# robomow_city120_terminal.net
KiCad netlist of a schematic drawn in EAGLE
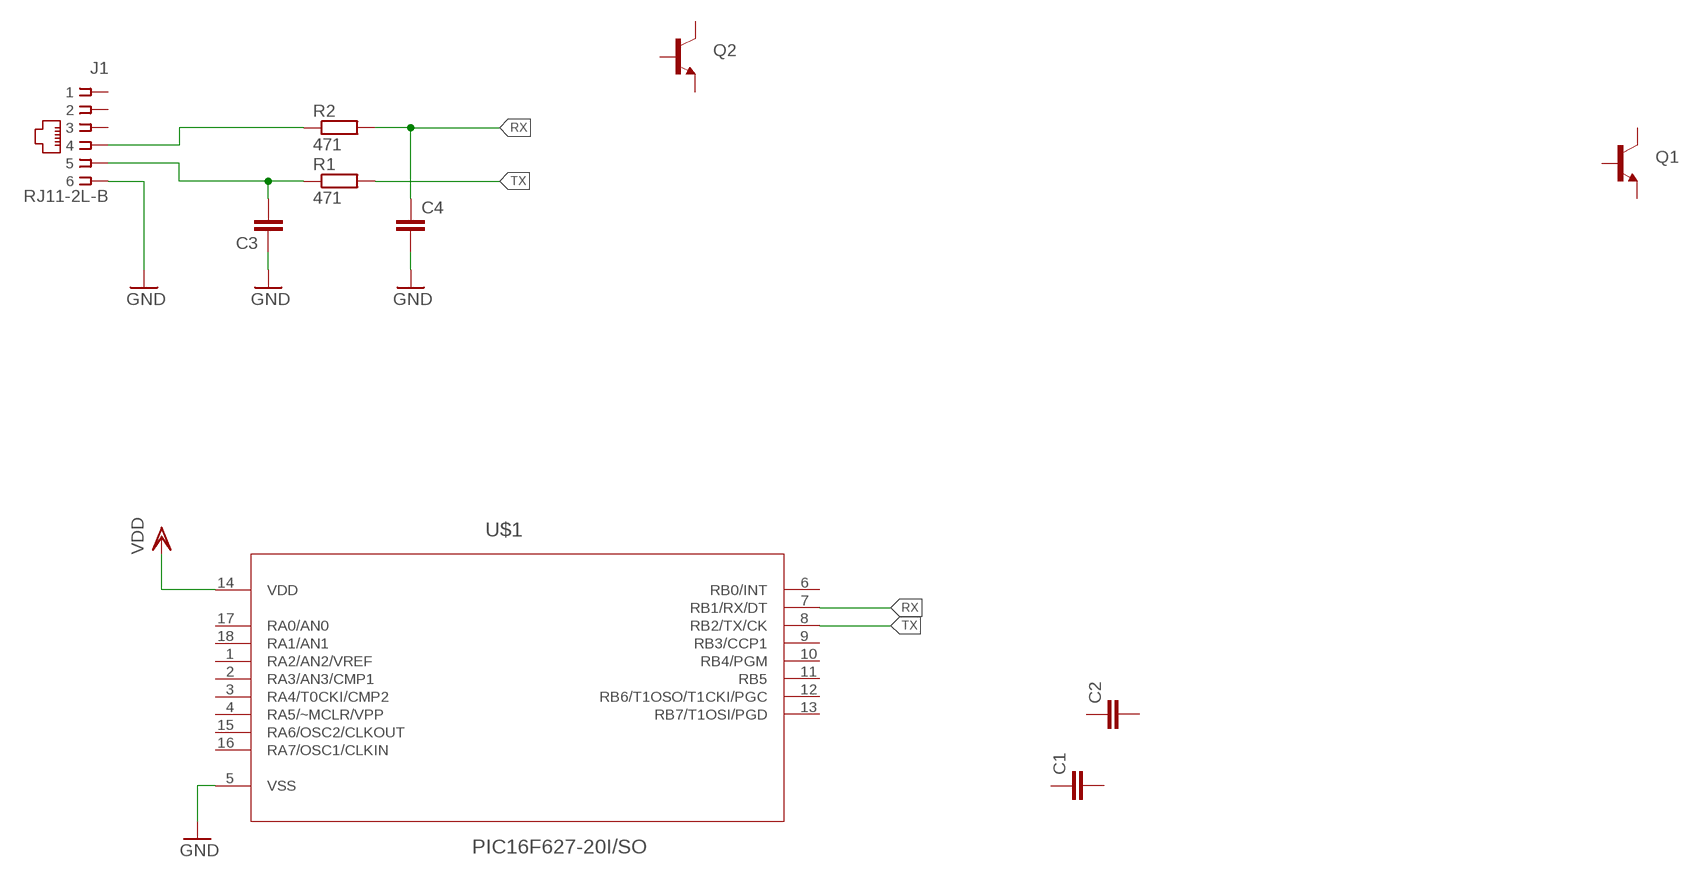
[diagram p0: schematic, sheet 1]

(export (version "E")
  (design (tool "Eeschema 10.0.6"))
  (components
    (comp (ref "C1")
      (value "C-EUC0805")
      (footprint "eagle-import:C0805")
      (libsource (lib "eagle-import") (part "C-EUC0805"))
    )
    (comp (ref "C2")
      (value "C-EUC0805")
      (footprint "eagle-import:C0805")
      (libsource (lib "eagle-import") (part "C-EUC0805"))
    )
    (comp (ref "C3")
      (value "C-EUC0805")
      (footprint "eagle-import:C0805")
      (libsource (lib "eagle-import") (part "C-EUC0805"))
    )
    (comp (ref "C4")
      (value "C-EUC0805")
      (footprint "eagle-import:C0805")
      (libsource (lib "eagle-import") (part "C-EUC0805"))
    )
    (comp (ref "J1")
      (value "RJ11-2L-B")
      (footprint "eagle-import:RJ11-NO_SHIELD")
      (fields (field (name "MF") "TYCO ELECTRONICS"))
      (libsource (lib "eagle-import") (part "RJ11-2L-B"))
    )
    (comp (ref "Q1")
      (value "TRANSISTOR_NPNSOT89")
      (footprint "eagle-import:SOT89")
      (libsource (lib "eagle-import") (part "TRANSISTOR_NPNSOT89"))
    )
    (comp (ref "Q2")
      (value "TRANSISTOR_NPNSOT89")
      (footprint "eagle-import:SOT89")
      (libsource (lib "eagle-import") (part "TRANSISTOR_NPNSOT89"))
    )
    (comp (ref "R1")
      (value "471")
      (footprint "eagle-import:R0805")
      (libsource (lib "eagle-import") (part "R-EU_R0805"))
    )
    (comp (ref "R2")
      (value "471")
      (footprint "eagle-import:R0805")
      (libsource (lib "eagle-import") (part "R-EU_R0805"))
    )
    (comp (ref "U$1")
      (value "PIC16F627-20I/SO")
      (footprint "eagle-import:SOIC127P1030X265-18N")
      (libsource (lib "eagle-import") (part "PIC16F627-20I/SO"))
    )
  )
  (nets
    (net (code "1") (name "GND") (class "Default")
      (node (ref "C3") (pin "1") (pinfunction "1_1") (pintype "passive"))
      (node (ref "C4") (pin "2") (pinfunction "2_2") (pintype "passive"))
      (node (ref "J1") (pin "6") (pinfunction "6_6") (pintype "passive"))
      (node (ref "U$1") (pin "5") (pinfunction "VSS_5") (pintype "power_in"))
    )
    (net (code "2") (name "Net-(C3-Pad2)") (class "Default")
      (node (ref "C3") (pin "2") (pinfunction "2_2") (pintype "passive"))
      (node (ref "J1") (pin "5") (pinfunction "5_5") (pintype "passive"))
      (node (ref "R1") (pin "1") (pinfunction "1_1") (pintype "passive"))
    )
    (net (code "3") (name "Net-(J1-Pad4)") (class "Default")
      (node (ref "J1") (pin "4") (pinfunction "4_4") (pintype "passive"))
      (node (ref "R2") (pin "1") (pinfunction "1_1") (pintype "passive"))
    )
    (net (code "4") (name "RX") (class "Default")
      (node (ref "C4") (pin "1") (pinfunction "1_1") (pintype "passive"))
      (node (ref "R2") (pin "2") (pinfunction "2_2") (pintype "passive"))
      (node (ref "U$1") (pin "7") (pinfunction "RB1/RX/DT_7") (pintype "bidirectional"))
    )
    (net (code "5") (name "TX") (class "Default")
      (node (ref "R1") (pin "2") (pinfunction "2_2") (pintype "passive"))
      (node (ref "U$1") (pin "8") (pinfunction "RB2/TX/CK_8") (pintype "bidirectional"))
    )
    (net (code "6") (name "VDD") (class "Default")
      (node (ref "U$1") (pin "14") (pinfunction "VDD_14") (pintype "power_in"))
    )
    (net (code "7") (name "unconnected-(C1-Pad1)") (class "Default")
      (node (ref "C1") (pin "1") (pinfunction "1_1") (pintype "passive"))
    )
    (net (code "8") (name "unconnected-(C1-Pad2)") (class "Default")
      (node (ref "C1") (pin "2") (pinfunction "2_2") (pintype "passive"))
    )
    (net (code "9") (name "unconnected-(C2-Pad1)") (class "Default")
      (node (ref "C2") (pin "1") (pinfunction "1_1") (pintype "passive"))
    )
    (net (code "10") (name "unconnected-(C2-Pad2)") (class "Default")
      (node (ref "C2") (pin "2") (pinfunction "2_2") (pintype "passive"))
    )
    (net (code "11") (name "unconnected-(J1-Pad1)") (class "Default")
      (node (ref "J1") (pin "1") (pinfunction "1_1") (pintype "passive"))
    )
    (net (code "12") (name "unconnected-(J1-Pad2)") (class "Default")
      (node (ref "J1") (pin "2") (pinfunction "2_2") (pintype "passive"))
    )
    (net (code "13") (name "unconnected-(J1-Pad3)") (class "Default")
      (node (ref "J1") (pin "3") (pinfunction "3_3") (pintype "passive"))
    )
    (net (code "14") (name "unconnected-(Q1-B-Pad1)") (class "Default")
      (node (ref "Q1") (pin "1") (pinfunction "B_1") (pintype "passive"))
    )
    (net (code "15") (name "unconnected-(Q1-C-Pad2)") (class "Default")
      (node (ref "Q1") (pin "2") (pinfunction "C_2") (pintype "passive"))
    )
    (net (code "16") (name "unconnected-(Q1-E-Pad3)") (class "Default")
      (node (ref "Q1") (pin "3") (pinfunction "E_3") (pintype "passive"))
    )
    (net (code "17") (name "unconnected-(Q2-B-Pad1)") (class "Default")
      (node (ref "Q2") (pin "1") (pinfunction "B_1") (pintype "passive"))
    )
    (net (code "18") (name "unconnected-(Q2-C-Pad2)") (class "Default")
      (node (ref "Q2") (pin "2") (pinfunction "C_2") (pintype "passive"))
    )
    (net (code "19") (name "unconnected-(Q2-E-Pad3)") (class "Default")
      (node (ref "Q2") (pin "3") (pinfunction "E_3") (pintype "passive"))
    )
    (net (code "20") (name "unconnected-(U$1-RA0{slash}AN0-Pad17)") (class "Default")
      (node (ref "U$1") (pin "17") (pinfunction "RA0/AN0_17") (pintype "bidirectional"))
    )
    (net (code "21") (name "unconnected-(U$1-RA1{slash}AN1-Pad18)") (class "Default")
      (node (ref "U$1") (pin "18") (pinfunction "RA1/AN1_18") (pintype "bidirectional"))
    )
    (net (code "22") (name "unconnected-(U$1-RA2{slash}AN2{slash}VREF-Pad1)") (class "Default")
      (node (ref "U$1") (pin "1") (pinfunction "RA2/AN2/VREF_1") (pintype "bidirectional"))
    )
    (net (code "23") (name "unconnected-(U$1-RA3{slash}AN3{slash}CMP1-Pad2)") (class "Default")
      (node (ref "U$1") (pin "2") (pinfunction "RA3/AN3/CMP1_2") (pintype "bidirectional"))
    )
    (net (code "24") (name "unconnected-(U$1-RA4{slash}T0CKI{slash}CMP2-Pad3)") (class "Default")
      (node (ref "U$1") (pin "3") (pinfunction "RA4/T0CKI/CMP2_3") (pintype "bidirectional"))
    )
    (net (code "25") (name "unconnected-(U$1-RA5{slash}~{MCLR{slash}VPP}-Pad4)") (class "Default")
      (node (ref "U$1") (pin "4") (pinfunction "RA5/~{MCLR/VPP}_4") (pintype "bidirectional"))
    )
    (net (code "26") (name "unconnected-(U$1-RA6{slash}OSC2{slash}CLKOUT-Pad15)") (class "Default")
      (node (ref "U$1") (pin "15") (pinfunction "RA6/OSC2/CLKOUT_15") (pintype "bidirectional"))
    )
    (net (code "27") (name "unconnected-(U$1-RA7{slash}OSC1{slash}CLKIN-Pad16)") (class "Default")
      (node (ref "U$1") (pin "16") (pinfunction "RA7/OSC1/CLKIN_16") (pintype "bidirectional"))
    )
    (net (code "28") (name "unconnected-(U$1-RB0{slash}INT-Pad6)") (class "Default")
      (node (ref "U$1") (pin "6") (pinfunction "RB0/INT_6") (pintype "bidirectional"))
    )
    (net (code "29") (name "unconnected-(U$1-RB3{slash}CCP1-Pad9)") (class "Default")
      (node (ref "U$1") (pin "9") (pinfunction "RB3/CCP1_9") (pintype "bidirectional"))
    )
    (net (code "30") (name "unconnected-(U$1-RB4{slash}PGM-Pad10)") (class "Default")
      (node (ref "U$1") (pin "10") (pinfunction "RB4/PGM_10") (pintype "bidirectional"))
    )
    (net (code "31") (name "unconnected-(U$1-RB5-Pad11)") (class "Default")
      (node (ref "U$1") (pin "11") (pinfunction "RB5_11") (pintype "bidirectional"))
    )
    (net (code "32") (name "unconnected-(U$1-RB6{slash}T1OSO{slash}T1CKI{slash}PGC-Pad12)") (class "Default")
      (node (ref "U$1") (pin "12") (pinfunction "RB6/T1OSO/T1CKI/PGC_12") (pintype "bidirectional"))
    )
    (net (code "33") (name "unconnected-(U$1-RB7{slash}T1OSI{slash}PGD-Pad13)") (class "Default")
      (node (ref "U$1") (pin "13") (pinfunction "RB7/T1OSI/PGD_13") (pintype "bidirectional"))
    )
  )
)
